# voice-card-controller-1.net
KiCad netlist of a schematic drawn in EAGLE
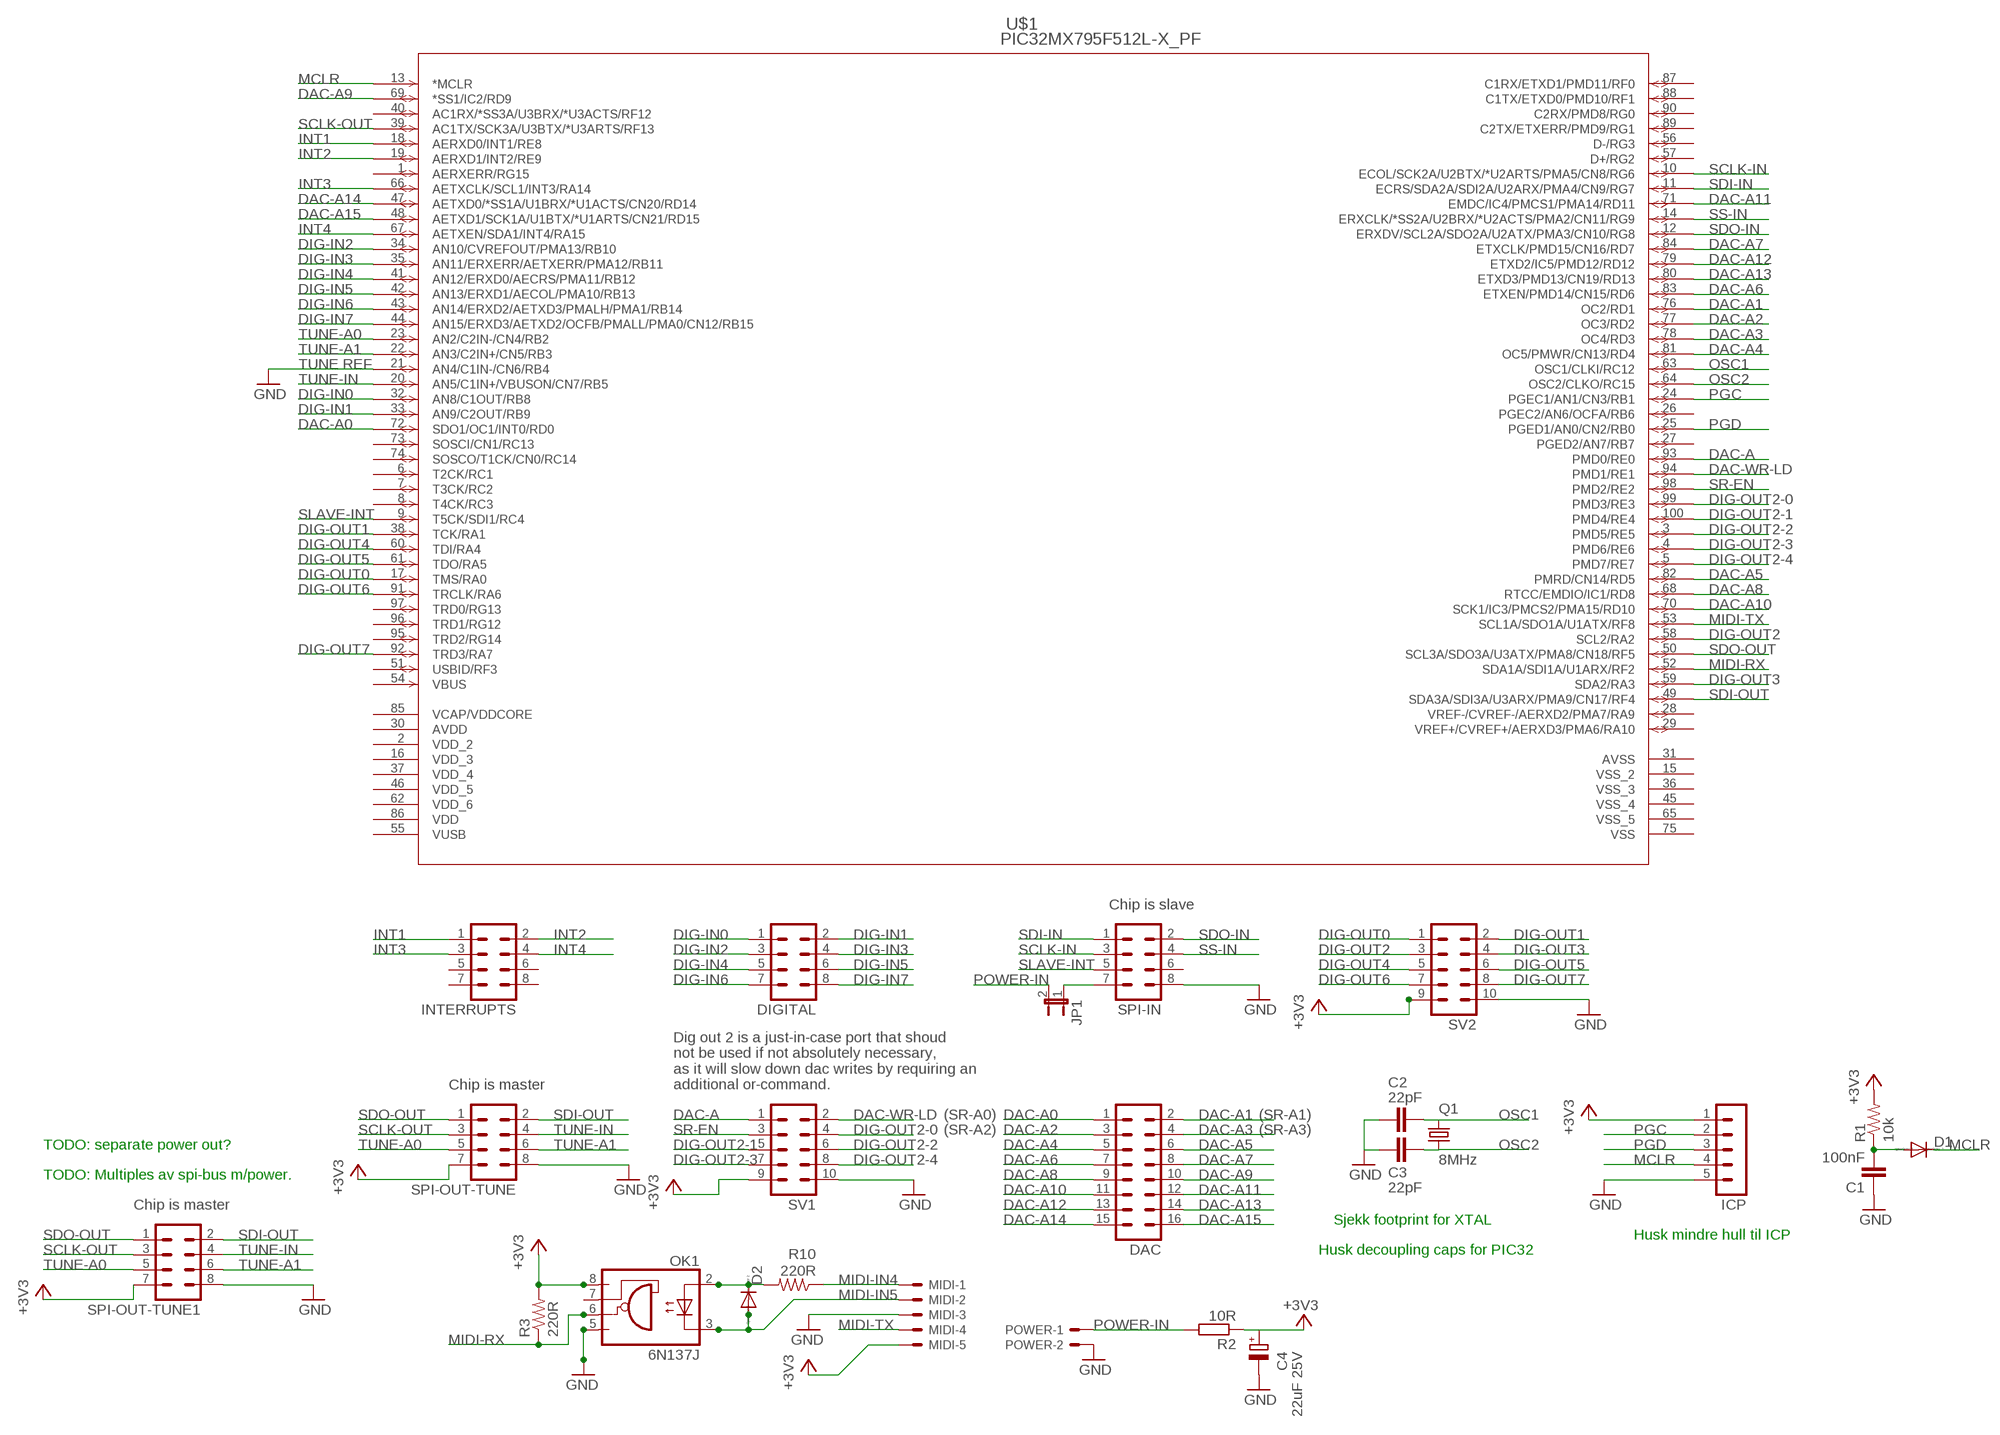
[diagram p0: schematic, sheet 1]

(export (version "E")
  (design (tool "Eeschema 10.0.6"))
  (components
    (comp (ref "C1")
      (value "100nF")
      (footprint "eagle-import:C0805")
      (libsource (lib "eagle-import") (part "C-EUC0805"))
    )
    (comp (ref "C2")
      (value "22pF")
      (footprint "eagle-import:C0805")
      (libsource (lib "eagle-import") (part "C-EUC0805"))
    )
    (comp (ref "C3")
      (value "22pF")
      (footprint "eagle-import:C0805")
      (libsource (lib "eagle-import") (part "C-EUC0805"))
    )
    (comp (ref "C4")
      (value "22uF 25V")
      (footprint "eagle-import:E2,5-5")
      (libsource (lib "eagle-import") (part "CPOL-EUE2.5-5"))
    )
    (comp (ref "D1")
      (value "DIODE-SOD80C")
      (footprint "eagle-import:SOD80C")
      (libsource (lib "eagle-import") (part "DIODE-SOD80C"))
    )
    (comp (ref "D2")
      (value "DIODE-SOD80C")
      (footprint "eagle-import:SOD80C")
      (libsource (lib "eagle-import") (part "DIODE-SOD80C"))
    )
    (comp (ref "DAC")
      (value "MA08-2")
      (footprint "eagle-import:MA08-2")
      (libsource (lib "eagle-import") (part "MA08-2"))
    )
    (comp (ref "DIGITAL")
      (value "MA04-2")
      (footprint "eagle-import:MA04-2")
      (libsource (lib "eagle-import") (part "MA04-2"))
    )
    (comp (ref "ICP")
      (value "MA05-1")
      (footprint "eagle-import:MA05-1")
      (libsource (lib "eagle-import") (part "MA05-1"))
    )
    (comp (ref "INTERRUPTS")
      (value "MA04-2")
      (footprint "eagle-import:MA04-2")
      (libsource (lib "eagle-import") (part "MA04-2"))
    )
    (comp (ref "JP1")
      (value "JP1E")
      (footprint "eagle-import:JP1")
      (libsource (lib "eagle-import") (part "JP1E"))
    )
    (comp (ref "MIDI")
      (value "22-23-2051")
      (footprint "eagle-import:22-23-2051")
      (fields (field (name "MF") "MOLEX"))
      (libsource (lib "eagle-import") (part "22-23-2051"))
    )
    (comp (ref "OK1")
      (value "6N137J")
      (footprint "eagle-import:DIL08-J")
      (libsource (lib "eagle-import") (part "6N137J"))
    )
    (comp (ref "POWER")
      (value "22-23-2021")
      (footprint "eagle-import:22-23-2021")
      (fields (field (name "MF") "MOLEX"))
      (libsource (lib "eagle-import") (part "22-23-2021"))
    )
    (comp (ref "Q1")
      (value "8MHz")
      (footprint "eagle-import:SM49")
      (libsource (lib "eagle-import") (part "CRYSTALSM49"))
    )
    (comp (ref "R1")
      (value "10k")
      (footprint "eagle-import:R0805")
      (libsource (lib "eagle-import") (part "R-US_R0805"))
    )
    (comp (ref "R2")
      (value "10R")
      (footprint "eagle-import:0207_7")
      (libsource (lib "eagle-import") (part "R-EU_0207/7"))
    )
    (comp (ref "R3")
      (value "220R")
      (footprint "eagle-import:R0805")
      (libsource (lib "eagle-import") (part "R-US_R0805"))
    )
    (comp (ref "R10")
      (value "220R")
      (footprint "eagle-import:R0805")
      (libsource (lib "eagle-import") (part "R-US_R0805"))
    )
    (comp (ref "SPI-IN")
      (value "MA04-2")
      (footprint "eagle-import:MA04-2")
      (libsource (lib "eagle-import") (part "MA04-2"))
    )
    (comp (ref "SPI-OUT-TUNE")
      (value "MA04-2")
      (footprint "eagle-import:MA04-2")
      (libsource (lib "eagle-import") (part "MA04-2"))
    )
    (comp (ref "SPI-OUT-TUNE1")
      (value "MA04-2")
      (footprint "eagle-import:MA04-2")
      (libsource (lib "eagle-import") (part "MA04-2"))
    )
    (comp (ref "SV1")
      (value "MA05-2")
      (footprint "eagle-import:MA05-2")
      (libsource (lib "eagle-import") (part "MA05-2"))
    )
    (comp (ref "SV2")
      (value "MA05-2")
      (footprint "eagle-import:MA05-2")
      (libsource (lib "eagle-import") (part "MA05-2"))
    )
    (comp (ref "U$1")
      (value "PIC32MX795F512L-X_PF")
      (footprint "eagle-import:TQFP100_14X14MC")
      (libsource (lib "eagle-import") (part "PIC32MX795F512L-X_PF"))
    )
  )
  (nets
    (net (code "1") (name "+3V3") (class "Default")
      (node (ref "C4") (pin "+") (pinfunction "+_+") (pintype "passive"))
      (node (ref "ICP") (pin "1") (pinfunction "1_1") (pintype "passive"))
      (node (ref "MIDI") (pin "5") (pinfunction "S_5") (pintype "passive"))
      (node (ref "OK1") (pin "8") (pinfunction "VCC_8") (pintype "passive"))
      (node (ref "R1") (pin "2") (pinfunction "2_2") (pintype "passive"))
      (node (ref "R2") (pin "1") (pinfunction "1_1") (pintype "passive"))
      (node (ref "R3") (pin "2") (pinfunction "2_2") (pintype "passive"))
      (node (ref "SPI-OUT-TUNE") (pin "7") (pinfunction "7_7") (pintype "passive"))
      (node (ref "SPI-OUT-TUNE1") (pin "7") (pinfunction "7_7") (pintype "passive"))
      (node (ref "SV1") (pin "9") (pinfunction "9_9") (pintype "passive"))
      (node (ref "SV2") (pin "9") (pinfunction "9_9") (pintype "passive"))
    )
    (net (code "2") (name "/AVDD") (class "Default")
      (node (ref "U$1") (pin "30") (pinfunction "AVDD_30") (pintype "power_in"))
    )
    (net (code "3") (name "/AVSS") (class "Default")
      (node (ref "U$1") (pin "31") (pinfunction "AVSS_31") (pintype "power_in"))
    )
    (net (code "4") (name "/DAC-A") (class "Default")
      (node (ref "SV1") (pin "1") (pinfunction "1_1") (pintype "passive"))
      (node (ref "U$1") (pin "93") (pinfunction "PMD0/RE0_93") (pintype "bidirectional"))
    )
    (net (code "5") (name "/DAC-A0") (class "Default")
      (node (ref "DAC") (pin "1") (pinfunction "1_1") (pintype "passive"))
      (node (ref "U$1") (pin "72") (pinfunction "SDO1/OC1/INT0/RD0_72") (pintype "bidirectional"))
    )
    (net (code "6") (name "/DAC-A1") (class "Default")
      (node (ref "DAC") (pin "2") (pinfunction "2_2") (pintype "passive"))
      (node (ref "U$1") (pin "76") (pinfunction "OC2/RD1_76") (pintype "bidirectional"))
    )
    (net (code "7") (name "/DAC-A2") (class "Default")
      (node (ref "DAC") (pin "3") (pinfunction "3_3") (pintype "passive"))
      (node (ref "U$1") (pin "77") (pinfunction "OC3/RD2_77") (pintype "bidirectional"))
    )
    (net (code "8") (name "/DAC-A3") (class "Default")
      (node (ref "DAC") (pin "4") (pinfunction "4_4") (pintype "passive"))
      (node (ref "U$1") (pin "78") (pinfunction "OC4/RD3_78") (pintype "bidirectional"))
    )
    (net (code "9") (name "/DAC-A4") (class "Default")
      (node (ref "DAC") (pin "5") (pinfunction "5_5") (pintype "passive"))
      (node (ref "U$1") (pin "81") (pinfunction "OC5/PMWR/CN13/RD4_81") (pintype "bidirectional"))
    )
    (net (code "10") (name "/DAC-A5") (class "Default")
      (node (ref "DAC") (pin "6") (pinfunction "6_6") (pintype "passive"))
      (node (ref "U$1") (pin "82") (pinfunction "PMRD/CN14/RD5_82") (pintype "bidirectional"))
    )
    (net (code "11") (name "/DAC-A6") (class "Default")
      (node (ref "DAC") (pin "7") (pinfunction "7_7") (pintype "passive"))
      (node (ref "U$1") (pin "83") (pinfunction "ETXEN/PMD14/CN15/RD6_83") (pintype "bidirectional"))
    )
    (net (code "12") (name "/DAC-A7") (class "Default")
      (node (ref "DAC") (pin "8") (pinfunction "8_8") (pintype "passive"))
      (node (ref "U$1") (pin "84") (pinfunction "ETXCLK/PMD15/CN16/RD7_84") (pintype "bidirectional"))
    )
    (net (code "13") (name "/DAC-A8") (class "Default")
      (node (ref "DAC") (pin "9") (pinfunction "9_9") (pintype "passive"))
      (node (ref "U$1") (pin "68") (pinfunction "RTCC/EMDIO/IC1/RD8_68") (pintype "bidirectional"))
    )
    (net (code "14") (name "/DAC-A9") (class "Default")
      (node (ref "DAC") (pin "10") (pinfunction "10_10") (pintype "passive"))
      (node (ref "U$1") (pin "69") (pinfunction "*SS1/IC2/RD9_69") (pintype "bidirectional"))
    )
    (net (code "15") (name "/DAC-A10") (class "Default")
      (node (ref "DAC") (pin "11") (pinfunction "11_11") (pintype "passive"))
      (node (ref "U$1") (pin "70") (pinfunction "SCK1/IC3/PMCS2/PMA15/RD10_70") (pintype "bidirectional"))
    )
    (net (code "16") (name "/DAC-A11") (class "Default")
      (node (ref "DAC") (pin "12") (pinfunction "12_12") (pintype "passive"))
      (node (ref "U$1") (pin "71") (pinfunction "EMDC/IC4/PMCS1/PMA14/RD11_71") (pintype "bidirectional"))
    )
    (net (code "17") (name "/DAC-A12") (class "Default")
      (node (ref "DAC") (pin "13") (pinfunction "13_13") (pintype "passive"))
      (node (ref "U$1") (pin "79") (pinfunction "ETXD2/IC5/PMD12/RD12_79") (pintype "bidirectional"))
    )
    (net (code "18") (name "/DAC-A13") (class "Default")
      (node (ref "DAC") (pin "14") (pinfunction "14_14") (pintype "passive"))
      (node (ref "U$1") (pin "80") (pinfunction "ETXD3/PMD13/CN19/RD13_80") (pintype "bidirectional"))
    )
    (net (code "19") (name "/DAC-A14") (class "Default")
      (node (ref "DAC") (pin "15") (pinfunction "15_15") (pintype "passive"))
      (node (ref "U$1") (pin "47") (pinfunction "AETXD0/*SS1A/U1BRX/*U1ACTS/CN20/RD14_47") (pintype "bidirectional"))
    )
    (net (code "20") (name "/DAC-A15") (class "Default")
      (node (ref "DAC") (pin "16") (pinfunction "16_16") (pintype "passive"))
      (node (ref "U$1") (pin "48") (pinfunction "AETXD1/SCK1A/U1BTX/*U1ARTS/CN21/RD15_48") (pintype "bidirectional"))
    )
    (net (code "21") (name "/DAC-WR-LD") (class "Default")
      (node (ref "SV1") (pin "2") (pinfunction "2_2") (pintype "passive"))
      (node (ref "U$1") (pin "94") (pinfunction "PMD1/RE1_94") (pintype "bidirectional"))
    )
    (net (code "22") (name "/DIG-IN0") (class "Default")
      (node (ref "DIGITAL") (pin "1") (pinfunction "1_1") (pintype "passive"))
      (node (ref "U$1") (pin "32") (pinfunction "AN8/C1OUT/RB8_32") (pintype "bidirectional"))
    )
    (net (code "23") (name "/DIG-IN1") (class "Default")
      (node (ref "DIGITAL") (pin "2") (pinfunction "2_2") (pintype "passive"))
      (node (ref "U$1") (pin "33") (pinfunction "AN9/C2OUT/RB9_33") (pintype "bidirectional"))
    )
    (net (code "24") (name "/DIG-IN2") (class "Default")
      (node (ref "DIGITAL") (pin "3") (pinfunction "3_3") (pintype "passive"))
      (node (ref "U$1") (pin "34") (pinfunction "AN10/CVREFOUT/PMA13/RB10_34") (pintype "bidirectional"))
    )
    (net (code "25") (name "/DIG-IN3") (class "Default")
      (node (ref "DIGITAL") (pin "4") (pinfunction "4_4") (pintype "passive"))
      (node (ref "U$1") (pin "35") (pinfunction "AN11/ERXERR/AETXERR/PMA12/RB11_35") (pintype "bidirectional"))
    )
    (net (code "26") (name "/DIG-IN4") (class "Default")
      (node (ref "DIGITAL") (pin "5") (pinfunction "5_5") (pintype "passive"))
      (node (ref "U$1") (pin "41") (pinfunction "AN12/ERXD0/AECRS/PMA11/RB12_41") (pintype "bidirectional"))
    )
    (net (code "27") (name "/DIG-IN5") (class "Default")
      (node (ref "DIGITAL") (pin "6") (pinfunction "6_6") (pintype "passive"))
      (node (ref "U$1") (pin "42") (pinfunction "AN13/ERXD1/AECOL/PMA10/RB13_42") (pintype "bidirectional"))
    )
    (net (code "28") (name "/DIG-IN6") (class "Default")
      (node (ref "DIGITAL") (pin "7") (pinfunction "7_7") (pintype "passive"))
      (node (ref "U$1") (pin "43") (pinfunction "AN14/ERXD2/AETXD3/PMALH/PMA1/RB14_43") (pintype "bidirectional"))
    )
    (net (code "29") (name "/DIG-IN7") (class "Default")
      (node (ref "DIGITAL") (pin "8") (pinfunction "8_8") (pintype "passive"))
      (node (ref "U$1") (pin "44") (pinfunction "AN15/ERXD3/AETXD2/OCFB/PMALL/PMA0/CN12/RB15_44") (pintype "bidirectional"))
    )
    (net (code "30") (name "/DIG-OUT0") (class "Default")
      (node (ref "SV2") (pin "1") (pinfunction "1_1") (pintype "passive"))
      (node (ref "U$1") (pin "17") (pinfunction "TMS/RA0_17") (pintype "bidirectional"))
    )
    (net (code "31") (name "/DIG-OUT1") (class "Default")
      (node (ref "SV2") (pin "2") (pinfunction "2_2") (pintype "passive"))
      (node (ref "U$1") (pin "38") (pinfunction "TCK/RA1_38") (pintype "bidirectional"))
    )
    (net (code "32") (name "/DIG-OUT2") (class "Default")
      (node (ref "SV2") (pin "3") (pinfunction "3_3") (pintype "passive"))
      (node (ref "U$1") (pin "58") (pinfunction "SCL2/RA2_58") (pintype "bidirectional"))
    )
    (net (code "33") (name "/DIG-OUT2-0") (class "Default")
      (node (ref "SV1") (pin "4") (pinfunction "4_4") (pintype "passive"))
      (node (ref "U$1") (pin "99") (pinfunction "PMD3/RE3_99") (pintype "bidirectional"))
    )
    (net (code "34") (name "/DIG-OUT2-1") (class "Default")
      (node (ref "SV1") (pin "5") (pinfunction "5_5") (pintype "passive"))
      (node (ref "U$1") (pin "100") (pinfunction "PMD4/RE4_100") (pintype "bidirectional"))
    )
    (net (code "35") (name "/DIG-OUT2-2") (class "Default")
      (node (ref "SV1") (pin "6") (pinfunction "6_6") (pintype "passive"))
      (node (ref "U$1") (pin "3") (pinfunction "PMD5/RE5_3") (pintype "bidirectional"))
    )
    (net (code "36") (name "/DIG-OUT2-3") (class "Default")
      (node (ref "SV1") (pin "7") (pinfunction "7_7") (pintype "passive"))
      (node (ref "U$1") (pin "4") (pinfunction "PMD6/RE6_4") (pintype "bidirectional"))
    )
    (net (code "37") (name "/DIG-OUT2-4") (class "Default")
      (node (ref "SV1") (pin "8") (pinfunction "8_8") (pintype "passive"))
      (node (ref "U$1") (pin "5") (pinfunction "PMD7/RE7_5") (pintype "bidirectional"))
    )
    (net (code "38") (name "/DIG-OUT3") (class "Default")
      (node (ref "SV2") (pin "4") (pinfunction "4_4") (pintype "passive"))
      (node (ref "U$1") (pin "59") (pinfunction "SDA2/RA3_59") (pintype "bidirectional"))
    )
    (net (code "39") (name "/DIG-OUT4") (class "Default")
      (node (ref "SV2") (pin "5") (pinfunction "5_5") (pintype "passive"))
      (node (ref "U$1") (pin "60") (pinfunction "TDI/RA4_60") (pintype "bidirectional"))
    )
    (net (code "40") (name "/DIG-OUT5") (class "Default")
      (node (ref "SV2") (pin "6") (pinfunction "6_6") (pintype "passive"))
      (node (ref "U$1") (pin "61") (pinfunction "TDO/RA5_61") (pintype "bidirectional"))
    )
    (net (code "41") (name "/DIG-OUT6") (class "Default")
      (node (ref "SV2") (pin "7") (pinfunction "7_7") (pintype "passive"))
      (node (ref "U$1") (pin "91") (pinfunction "TRCLK/RA6_91") (pintype "bidirectional"))
    )
    (net (code "42") (name "/DIG-OUT7") (class "Default")
      (node (ref "SV2") (pin "8") (pinfunction "8_8") (pintype "passive"))
      (node (ref "U$1") (pin "92") (pinfunction "TRD3/RA7_92") (pintype "bidirectional"))
    )
    (net (code "43") (name "/INT1") (class "Default")
      (node (ref "INTERRUPTS") (pin "1") (pinfunction "1_1") (pintype "passive"))
      (node (ref "U$1") (pin "18") (pinfunction "AERXD0/INT1/RE8_18") (pintype "bidirectional"))
    )
    (net (code "44") (name "/INT2") (class "Default")
      (node (ref "INTERRUPTS") (pin "2") (pinfunction "2_2") (pintype "passive"))
      (node (ref "U$1") (pin "19") (pinfunction "AERXD1/INT2/RE9_19") (pintype "bidirectional"))
    )
    (net (code "45") (name "/INT3") (class "Default")
      (node (ref "INTERRUPTS") (pin "3") (pinfunction "3_3") (pintype "passive"))
      (node (ref "U$1") (pin "66") (pinfunction "AETXCLK/SCL1/INT3/RA14_66") (pintype "bidirectional"))
    )
    (net (code "46") (name "/INT4") (class "Default")
      (node (ref "INTERRUPTS") (pin "4") (pinfunction "4_4") (pintype "passive"))
      (node (ref "U$1") (pin "67") (pinfunction "AETXEN/SDA1/INT4/RA15_67") (pintype "bidirectional"))
    )
    (net (code "47") (name "/MCLR") (class "Default")
      (node (ref "D1") (pin "C") (pinfunction "C_C") (pintype "passive"))
      (node (ref "ICP") (pin "4") (pinfunction "4_4") (pintype "passive"))
      (node (ref "U$1") (pin "13") (pinfunction "*MCLR_13") (pintype "input"))
    )
    (net (code "48") (name "/MIDI-IN4") (class "Default")
      (node (ref "MIDI") (pin "1") (pinfunction "S_1") (pintype "passive"))
      (node (ref "R10") (pin "1") (pinfunction "1_1") (pintype "passive"))
    )
    (net (code "49") (name "/MIDI-IN5") (class "Default")
      (node (ref "D2") (pin "A") (pinfunction "A_A") (pintype "passive"))
      (node (ref "MIDI") (pin "2") (pinfunction "S_2") (pintype "passive"))
      (node (ref "OK1") (pin "3") (pinfunction "C_3") (pintype "passive"))
    )
    (net (code "50") (name "/MIDI-RX") (class "Default")
      (node (ref "OK1") (pin "6") (pinfunction "VO_6") (pintype "passive"))
      (node (ref "R3") (pin "1") (pinfunction "1_1") (pintype "passive"))
      (node (ref "U$1") (pin "52") (pinfunction "SDA1A/SDI1A/U1ARX/RF2_52") (pintype "bidirectional"))
    )
    (net (code "51") (name "/MIDI-TX") (class "Default")
      (node (ref "MIDI") (pin "4") (pinfunction "S_4") (pintype "passive"))
      (node (ref "U$1") (pin "53") (pinfunction "SCL1A/SDO1A/U1ATX/RF8_53") (pintype "bidirectional"))
    )
    (net (code "52") (name "/OSC1") (class "Default")
      (node (ref "C2") (pin "1") (pinfunction "1_1") (pintype "passive"))
      (node (ref "Q1") (pin "2") (pinfunction "2_2") (pintype "passive"))
      (node (ref "U$1") (pin "63") (pinfunction "OSC1/CLKI/RC12_63") (pintype "bidirectional"))
    )
    (net (code "53") (name "/OSC2") (class "Default")
      (node (ref "C3") (pin "1") (pinfunction "1_1") (pintype "passive"))
      (node (ref "Q1") (pin "1") (pinfunction "1_1") (pintype "passive"))
      (node (ref "U$1") (pin "64") (pinfunction "OSC2/CLKO/RC15_64") (pintype "bidirectional"))
    )
    (net (code "54") (name "/PGC") (class "Default")
      (node (ref "ICP") (pin "2") (pinfunction "2_2") (pintype "passive"))
      (node (ref "U$1") (pin "24") (pinfunction "PGEC1/AN1/CN3/RB1_24") (pintype "bidirectional"))
    )
    (net (code "55") (name "/PGD") (class "Default")
      (node (ref "ICP") (pin "3") (pinfunction "3_3") (pintype "passive"))
      (node (ref "U$1") (pin "25") (pinfunction "PGED1/AN0/CN2/RB0_25") (pintype "bidirectional"))
    )
    (net (code "56") (name "/POWER-IN") (class "Default")
      (node (ref "JP1") (pin "2") (pinfunction "2_2") (pintype "passive"))
      (node (ref "POWER") (pin "1") (pinfunction "S_1") (pintype "passive"))
      (node (ref "R2") (pin "2") (pinfunction "2_2") (pintype "passive"))
    )
    (net (code "57") (name "/SCLK-IN") (class "Default")
      (node (ref "SPI-IN") (pin "3") (pinfunction "3_3") (pintype "passive"))
      (node (ref "U$1") (pin "10") (pinfunction "ECOL/SCK2A/U2BTX/*U2ARTS/PMA5/CN8/RG6_10") (pintype "bidirectional"))
    )
    (net (code "58") (name "/SCLK-OUT") (class "Default")
      (node (ref "SPI-OUT-TUNE") (pin "3") (pinfunction "3_3") (pintype "passive"))
      (node (ref "SPI-OUT-TUNE1") (pin "3") (pinfunction "3_3") (pintype "passive"))
      (node (ref "U$1") (pin "39") (pinfunction "AC1TX/SCK3A/U3BTX/*U3ARTS/RF13_39") (pintype "bidirectional"))
    )
    (net (code "59") (name "/SDI-IN") (class "Default")
      (node (ref "SPI-IN") (pin "1") (pinfunction "1_1") (pintype "passive"))
      (node (ref "U$1") (pin "11") (pinfunction "ECRS/SDA2A/SDI2A/U2ARX/PMA4/CN9/RG7_11") (pintype "bidirectional"))
    )
    (net (code "60") (name "/SDI-OUT") (class "Default")
      (node (ref "SPI-OUT-TUNE") (pin "2") (pinfunction "2_2") (pintype "passive"))
      (node (ref "SPI-OUT-TUNE1") (pin "2") (pinfunction "2_2") (pintype "passive"))
      (node (ref "U$1") (pin "49") (pinfunction "SDA3A/SDI3A/U3ARX/PMA9/CN17/RF4_49") (pintype "bidirectional"))
    )
    (net (code "61") (name "/SDO-IN") (class "Default")
      (node (ref "SPI-IN") (pin "2") (pinfunction "2_2") (pintype "passive"))
      (node (ref "U$1") (pin "12") (pinfunction "ERXDV/SCL2A/SDO2A/U2ATX/PMA3/CN10/RG8_12") (pintype "bidirectional"))
    )
    (net (code "62") (name "/SDO-OUT") (class "Default")
      (node (ref "SPI-OUT-TUNE") (pin "1") (pinfunction "1_1") (pintype "passive"))
      (node (ref "SPI-OUT-TUNE1") (pin "1") (pinfunction "1_1") (pintype "passive"))
      (node (ref "U$1") (pin "50") (pinfunction "SCL3A/SDO3A/U3ATX/PMA8/CN18/RF5_50") (pintype "bidirectional"))
    )
    (net (code "63") (name "/SLAVE-INT") (class "Default")
      (node (ref "SPI-IN") (pin "5") (pinfunction "5_5") (pintype "passive"))
      (node (ref "U$1") (pin "9") (pinfunction "T5CK/SDI1/RC4_9") (pintype "bidirectional"))
    )
    (net (code "64") (name "/SR-EN") (class "Default")
      (node (ref "SV1") (pin "3") (pinfunction "3_3") (pintype "passive"))
      (node (ref "U$1") (pin "98") (pinfunction "PMD2/RE2_98") (pintype "bidirectional"))
    )
    (net (code "65") (name "/SS-IN") (class "Default")
      (node (ref "SPI-IN") (pin "4") (pinfunction "4_4") (pintype "passive"))
      (node (ref "U$1") (pin "14") (pinfunction "ERXCLK/*SS2A/U2BRX/*U2ACTS/PMA2/CN11/RG9_14") (pintype "bidirectional"))
    )
    (net (code "66") (name "/TUNE-A0") (class "Default")
      (node (ref "SPI-OUT-TUNE") (pin "5") (pinfunction "5_5") (pintype "passive"))
      (node (ref "SPI-OUT-TUNE1") (pin "5") (pinfunction "5_5") (pintype "passive"))
      (node (ref "U$1") (pin "23") (pinfunction "AN2/C2IN-/CN4/RB2_23") (pintype "bidirectional"))
    )
    (net (code "67") (name "/TUNE-A1") (class "Default")
      (node (ref "SPI-OUT-TUNE") (pin "6") (pinfunction "6_6") (pintype "passive"))
      (node (ref "SPI-OUT-TUNE1") (pin "6") (pinfunction "6_6") (pintype "passive"))
      (node (ref "U$1") (pin "22") (pinfunction "AN3/C2IN+/CN5/RB3_22") (pintype "bidirectional"))
    )
    (net (code "68") (name "/TUNE-IN") (class "Default")
      (node (ref "SPI-OUT-TUNE") (pin "4") (pinfunction "4_4") (pintype "passive"))
      (node (ref "SPI-OUT-TUNE1") (pin "4") (pinfunction "4_4") (pintype "passive"))
      (node (ref "U$1") (pin "20") (pinfunction "AN5/C1IN+/VBUSON/CN7/RB5_20") (pintype "bidirectional"))
    )
    (net (code "69") (name "/VCAP{slash}VDDCORE") (class "Default")
      (node (ref "U$1") (pin "85") (pinfunction "VCAP/VDDCORE_85") (pintype "power_in"))
    )
    (net (code "70") (name "/VDD") (class "Default")
      (node (ref "U$1") (pin "86") (pinfunction "VDD_86") (pintype "power_in"))
    )
    (net (code "71") (name "/VDD_2") (class "Default")
      (node (ref "U$1") (pin "2") (pinfunction "VDD_2_2") (pintype "power_in"))
    )
    (net (code "72") (name "/VDD_3") (class "Default")
      (node (ref "U$1") (pin "16") (pinfunction "VDD_3_16") (pintype "power_in"))
    )
    (net (code "73") (name "/VDD_4") (class "Default")
      (node (ref "U$1") (pin "37") (pinfunction "VDD_4_37") (pintype "power_in"))
    )
    (net (code "74") (name "/VDD_5") (class "Default")
      (node (ref "U$1") (pin "46") (pinfunction "VDD_5_46") (pintype "power_in"))
    )
    (net (code "75") (name "/VDD_6") (class "Default")
      (node (ref "U$1") (pin "62") (pinfunction "VDD_6_62") (pintype "power_in"))
    )
    (net (code "76") (name "/VSS") (class "Default")
      (node (ref "U$1") (pin "75") (pinfunction "VSS_75") (pintype "power_in"))
    )
    (net (code "77") (name "/VSS_2") (class "Default")
      (node (ref "U$1") (pin "15") (pinfunction "VSS_2_15") (pintype "power_in"))
    )
    (net (code "78") (name "/VSS_3") (class "Default")
      (node (ref "U$1") (pin "36") (pinfunction "VSS_3_36") (pintype "power_in"))
    )
    (net (code "79") (name "/VSS_4") (class "Default")
      (node (ref "U$1") (pin "45") (pinfunction "VSS_4_45") (pintype "power_in"))
    )
    (net (code "80") (name "/VSS_5") (class "Default")
      (node (ref "U$1") (pin "65") (pinfunction "VSS_5_65") (pintype "power_in"))
    )
    (net (code "81") (name "/VUSB") (class "Default")
      (node (ref "U$1") (pin "55") (pinfunction "VUSB_55") (pintype "power_in"))
    )
    (net (code "82") (name "GND") (class "Default")
      (node (ref "C1") (pin "1") (pinfunction "1_1") (pintype "passive"))
      (node (ref "C2") (pin "2") (pinfunction "2_2") (pintype "passive"))
      (node (ref "C3") (pin "2") (pinfunction "2_2") (pintype "passive"))
      (node (ref "C4") (pin "-") (pinfunction "-_-") (pintype "passive"))
      (node (ref "ICP") (pin "5") (pinfunction "5_5") (pintype "passive"))
      (node (ref "MIDI") (pin "3") (pinfunction "S_3") (pintype "passive"))
      (node (ref "OK1") (pin "5") (pinfunction "GND_5") (pintype "passive"))
      (node (ref "POWER") (pin "2") (pinfunction "S_2") (pintype "passive"))
      (node (ref "SPI-IN") (pin "8") (pinfunction "8_8") (pintype "passive"))
      (node (ref "SPI-OUT-TUNE") (pin "8") (pinfunction "8_8") (pintype "passive"))
      (node (ref "SPI-OUT-TUNE1") (pin "8") (pinfunction "8_8") (pintype "passive"))
      (node (ref "SV1") (pin "10") (pinfunction "10_10") (pintype "passive"))
      (node (ref "SV2") (pin "10") (pinfunction "10_10") (pintype "passive"))
      (node (ref "U$1") (pin "21") (pinfunction "AN4/C1IN-/CN6/RB4_21") (pintype "bidirectional"))
    )
    (net (code "83") (name "Net-(C1-Pad2)") (class "Default")
      (node (ref "C1") (pin "2") (pinfunction "2_2") (pintype "passive"))
      (node (ref "D1") (pin "A") (pinfunction "A_A") (pintype "passive"))
      (node (ref "R1") (pin "1") (pinfunction "1_1") (pintype "passive"))
    )
    (net (code "84") (name "Net-(JP1-Pad1)") (class "Default")
      (node (ref "JP1") (pin "1") (pinfunction "1_1") (pintype "passive"))
      (node (ref "SPI-IN") (pin "7") (pinfunction "7_7") (pintype "passive"))
    )
    (net (code "85") (name "Net-(OK1-A)") (class "Default")
      (node (ref "D2") (pin "C") (pinfunction "C_C") (pintype "passive"))
      (node (ref "OK1") (pin "2") (pinfunction "A_2") (pintype "passive"))
      (node (ref "R10") (pin "2") (pinfunction "2_2") (pintype "passive"))
    )
    (net (code "86") (name "unconnected-(INTERRUPTS-Pad5)") (class "Default")
      (node (ref "INTERRUPTS") (pin "5") (pinfunction "5_5") (pintype "passive"))
    )
    (net (code "87") (name "unconnected-(INTERRUPTS-Pad6)") (class "Default")
      (node (ref "INTERRUPTS") (pin "6") (pinfunction "6_6") (pintype "passive"))
    )
    (net (code "88") (name "unconnected-(INTERRUPTS-Pad7)") (class "Default")
      (node (ref "INTERRUPTS") (pin "7") (pinfunction "7_7") (pintype "passive"))
    )
    (net (code "89") (name "unconnected-(INTERRUPTS-Pad8)") (class "Default")
      (node (ref "INTERRUPTS") (pin "8") (pinfunction "8_8") (pintype "passive"))
    )
    (net (code "90") (name "unconnected-(OK1-VE-Pad7)") (class "Default")
      (node (ref "OK1") (pin "7") (pinfunction "VE_7") (pintype "passive"))
    )
    (net (code "91") (name "unconnected-(SPI-IN-Pad6)") (class "Default")
      (node (ref "SPI-IN") (pin "6") (pinfunction "6_6") (pintype "passive"))
    )
    (net (code "92") (name "unconnected-(U$1-AC1RX{slash}*SS3A{slash}U3BRX{slash}*U3ACTS{slash}RF12-Pad40)") (class "Default")
      (node (ref "U$1") (pin "40") (pinfunction "AC1RX/*SS3A/U3BRX/*U3ACTS/RF12_40") (pintype "bidirectional"))
    )
    (net (code "93") (name "unconnected-(U$1-AERXERR{slash}RG15-Pad1)") (class "Default")
      (node (ref "U$1") (pin "1") (pinfunction "AERXERR/RG15_1") (pintype "bidirectional"))
    )
    (net (code "94") (name "unconnected-(U$1-C1RX{slash}ETXD1{slash}PMD11{slash}RF0-Pad87)") (class "Default")
      (node (ref "U$1") (pin "87") (pinfunction "C1RX/ETXD1/PMD11/RF0_87") (pintype "bidirectional"))
    )
    (net (code "95") (name "unconnected-(U$1-C1TX{slash}ETXD0{slash}PMD10{slash}RF1-Pad88)") (class "Default")
      (node (ref "U$1") (pin "88") (pinfunction "C1TX/ETXD0/PMD10/RF1_88") (pintype "bidirectional"))
    )
    (net (code "96") (name "unconnected-(U$1-C2RX{slash}PMD8{slash}RG0-Pad90)") (class "Default")
      (node (ref "U$1") (pin "90") (pinfunction "C2RX/PMD8/RG0_90") (pintype "bidirectional"))
    )
    (net (code "97") (name "unconnected-(U$1-C2TX{slash}ETXERR{slash}PMD9{slash}RG1-Pad89)") (class "Default")
      (node (ref "U$1") (pin "89") (pinfunction "C2TX/ETXERR/PMD9/RG1_89") (pintype "bidirectional"))
    )
    (net (code "98") (name "unconnected-(U$1-D+{slash}RG2-Pad57)") (class "Default")
      (node (ref "U$1") (pin "57") (pinfunction "D+/RG2_57") (pintype "bidirectional"))
    )
    (net (code "99") (name "unconnected-(U$1-D-{slash}RG3-Pad56)") (class "Default")
      (node (ref "U$1") (pin "56") (pinfunction "D-/RG3_56") (pintype "bidirectional"))
    )
    (net (code "100") (name "unconnected-(U$1-PGEC2{slash}AN6{slash}OCFA{slash}RB6-Pad26)") (class "Default")
      (node (ref "U$1") (pin "26") (pinfunction "PGEC2/AN6/OCFA/RB6_26") (pintype "bidirectional"))
    )
    (net (code "101") (name "unconnected-(U$1-PGED2{slash}AN7{slash}RB7-Pad27)") (class "Default")
      (node (ref "U$1") (pin "27") (pinfunction "PGED2/AN7/RB7_27") (pintype "bidirectional"))
    )
    (net (code "102") (name "unconnected-(U$1-SOSCI{slash}CN1{slash}RC13-Pad73)") (class "Default")
      (node (ref "U$1") (pin "73") (pinfunction "SOSCI/CN1/RC13_73") (pintype "bidirectional"))
    )
    (net (code "103") (name "unconnected-(U$1-SOSCO{slash}T1CK{slash}CN0{slash}RC14-Pad74)") (class "Default")
      (node (ref "U$1") (pin "74") (pinfunction "SOSCO/T1CK/CN0/RC14_74") (pintype "bidirectional"))
    )
    (net (code "104") (name "unconnected-(U$1-T2CK{slash}RC1-Pad6)") (class "Default")
      (node (ref "U$1") (pin "6") (pinfunction "T2CK/RC1_6") (pintype "bidirectional"))
    )
    (net (code "105") (name "unconnected-(U$1-T3CK{slash}RC2-Pad7)") (class "Default")
      (node (ref "U$1") (pin "7") (pinfunction "T3CK/RC2_7") (pintype "bidirectional"))
    )
    (net (code "106") (name "unconnected-(U$1-T4CK{slash}RC3-Pad8)") (class "Default")
      (node (ref "U$1") (pin "8") (pinfunction "T4CK/RC3_8") (pintype "bidirectional"))
    )
    (net (code "107") (name "unconnected-(U$1-TRD0{slash}RG13-Pad97)") (class "Default")
      (node (ref "U$1") (pin "97") (pinfunction "TRD0/RG13_97") (pintype "bidirectional"))
    )
    (net (code "108") (name "unconnected-(U$1-TRD1{slash}RG12-Pad96)") (class "Default")
      (node (ref "U$1") (pin "96") (pinfunction "TRD1/RG12_96") (pintype "bidirectional"))
    )
    (net (code "109") (name "unconnected-(U$1-TRD2{slash}RG14-Pad95)") (class "Default")
      (node (ref "U$1") (pin "95") (pinfunction "TRD2/RG14_95") (pintype "bidirectional"))
    )
    (net (code "110") (name "unconnected-(U$1-USBID{slash}RF3-Pad51)") (class "Default")
      (node (ref "U$1") (pin "51") (pinfunction "USBID/RF3_51") (pintype "bidirectional"))
    )
    (net (code "111") (name "unconnected-(U$1-VBUS-Pad54)") (class "Default")
      (node (ref "U$1") (pin "54") (pinfunction "VBUS_54") (pintype "input"))
    )
    (net (code "112") (name "unconnected-(U$1-VREF+{slash}CVREF+{slash}AERXD3{slash}PMA6{slash}RA10-Pad29)") (class "Default")
      (node (ref "U$1") (pin "29") (pinfunction "VREF+/CVREF+/AERXD3/PMA6/RA10_29") (pintype "bidirectional"))
    )
    (net (code "113") (name "unconnected-(U$1-VREF-{slash}CVREF-{slash}AERXD2{slash}PMA7{slash}RA9-Pad28)") (class "Default")
      (node (ref "U$1") (pin "28") (pinfunction "VREF-/CVREF-/AERXD2/PMA7/RA9_28") (pintype "bidirectional"))
    )
  )
)
